# Link232-wifi.net
KiCad netlist of a schematic drawn in EAGLE
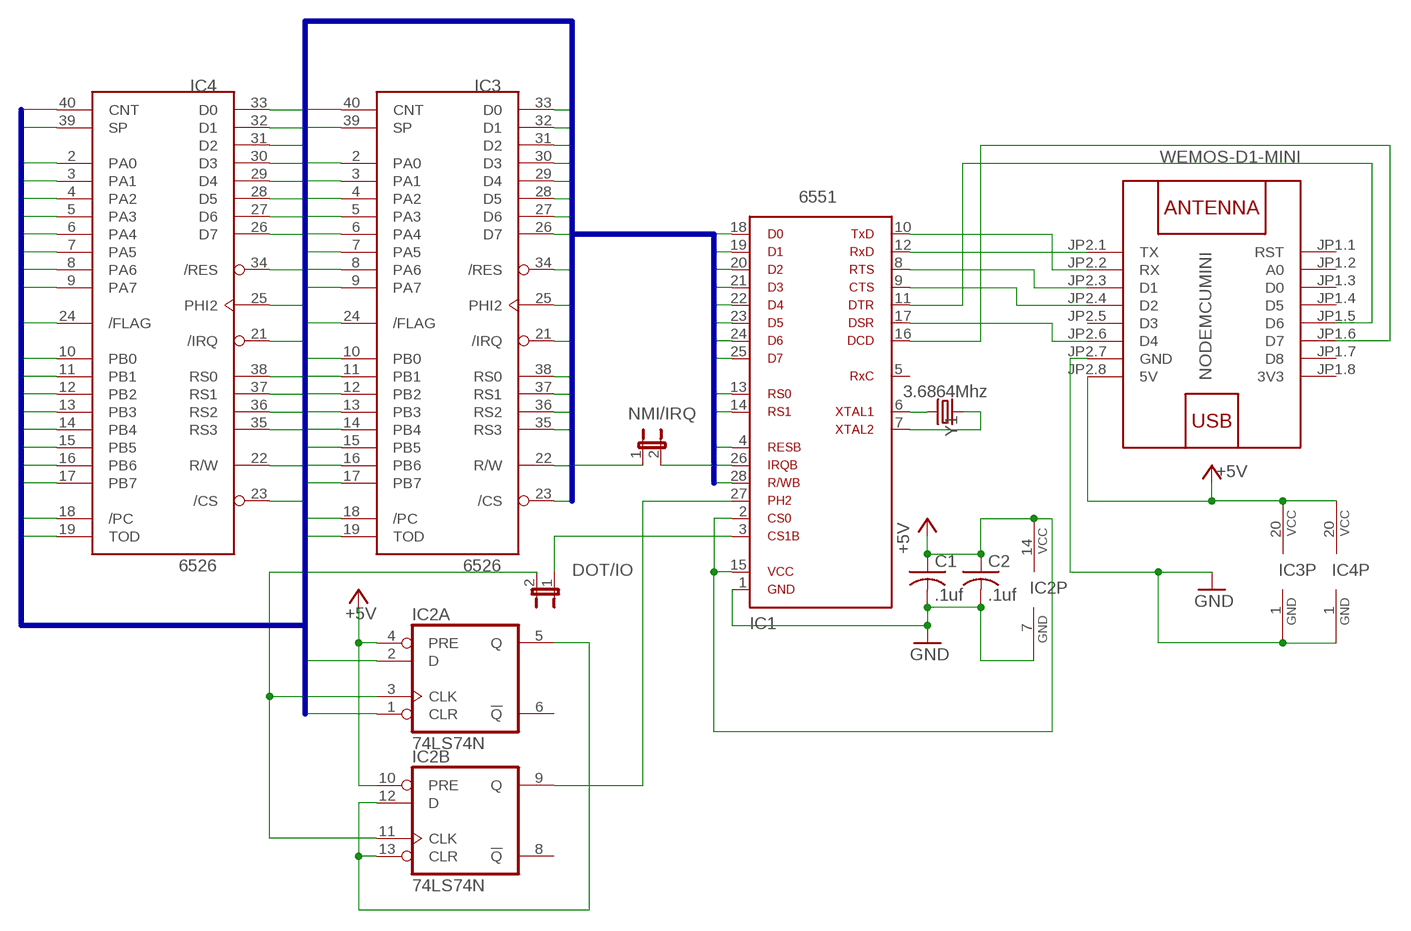
[diagram p0: schematic, sheet 1]

(export (version "E")
  (design (tool "Eeschema 10.0.6"))
  (components
    (comp (ref "C1")
      (value ".1uf")
      (footprint "eagle-import:C050-024X044")
      (libsource (lib "eagle-import") (part "C-US050-024X044"))
    )
    (comp (ref "C2")
      (value ".1uf")
      (footprint "eagle-import:C050-024X044")
      (libsource (lib "eagle-import") (part "C-US050-024X044"))
    )
    (comp (ref "IC1")
      (value "6551")
      (footprint "eagle-import:6551")
      (libsource (lib "eagle-import") (part "6551"))
    )
    (comp (ref "IC2")
      (value "74LS74N")
      (footprint "eagle-import:DIL14")
      (libsource (lib "eagle-import") (part "7474NLS"))
    )
    (comp (ref "IC3")
      (value "6526")
      (footprint "eagle-import:DIP40")
      (libsource (lib "eagle-import") (part "6526"))
    )
    (comp (ref "IC4")
      (value "6526")
      (footprint "eagle-import:DIP40")
      (libsource (lib "eagle-import") (part "6526"))
    )
    (comp (ref "JP1")
      (value "NMI/IRQ")
      (footprint "eagle-import:JP1")
      (libsource (lib "eagle-import") (part "JP1E"))
    )
    (comp (ref "JP2")
      (value "DOT/IO")
      (footprint "eagle-import:JP1")
      (libsource (lib "eagle-import") (part "JP1E"))
    )
    (comp (ref "NODEMCUMINI")
      (value "WEMOS-D1-MINI")
      (footprint "eagle-import:WEMOS-D1-MINI")
      (libsource (lib "eagle-import") (part "WEMOS-D1-MINI"))
    )
    (comp (ref "Y1")
      (value "3.6864Mhz")
      (footprint "eagle-import:HC49US")
      (libsource (lib "eagle-import") (part "CRYSTALPTH-HC49US"))
    )
  )
  (nets
    (net (code "1") (name "+5V") (class "Default")
      (node (ref "C1") (pin "1") (pinfunction "1_1") (pintype "passive"))
      (node (ref "C2") (pin "1") (pinfunction "1_1") (pintype "passive"))
      (node (ref "IC1") (pin "15") (pinfunction "15_15") (pintype "passive"))
      (node (ref "IC1") (pin "2") (pinfunction "2_2") (pintype "passive"))
      (node (ref "IC2") (pin "10") (pinfunction "PRE_10") (pintype "input"))
      (node (ref "IC2") (pin "14") (pinfunction "VCC_14") (pintype "power_in"))
      (node (ref "IC2") (pin "4") (pinfunction "PRE_4") (pintype "input"))
      (node (ref "IC3") (pin "20") (pinfunction "VCC_20") (pintype "power_in"))
      (node (ref "IC4") (pin "20") (pinfunction "VCC_20") (pintype "power_in"))
      (node (ref "NODEMCUMINI") (pin "JP2.8") (pinfunction "5V_JP2.8") (pintype "power_in"))
    )
    (net (code "2") (name "/3V3") (class "Default")
      (node (ref "NODEMCUMINI") (pin "JP1.8") (pinfunction "3V3_JP1.8") (pintype "power_in"))
    )
    (net (code "3") (name "/CNT") (class "Default")
      (node (ref "IC3") (pin "40") (pinfunction "CNT_40") (pintype "input"))
      (node (ref "IC4") (pin "40") (pinfunction "CNT_40") (pintype "input"))
    )
    (net (code "4") (name "/D0") (class "Default")
      (node (ref "IC1") (pin "18") (pinfunction "18_18") (pintype "passive"))
      (node (ref "IC3") (pin "33") (pinfunction "D0_33") (pintype "bidirectional"))
      (node (ref "IC4") (pin "33") (pinfunction "D0_33") (pintype "bidirectional"))
    )
    (net (code "5") (name "/D1") (class "Default")
      (node (ref "IC1") (pin "19") (pinfunction "19_19") (pintype "passive"))
      (node (ref "IC3") (pin "32") (pinfunction "D1_32") (pintype "bidirectional"))
      (node (ref "IC4") (pin "32") (pinfunction "D1_32") (pintype "bidirectional"))
    )
    (net (code "6") (name "/D2") (class "Default")
      (node (ref "IC1") (pin "20") (pinfunction "20_20") (pintype "passive"))
      (node (ref "IC3") (pin "31") (pinfunction "D2_31") (pintype "bidirectional"))
      (node (ref "IC4") (pin "31") (pinfunction "D2_31") (pintype "bidirectional"))
    )
    (net (code "7") (name "/D3") (class "Default")
      (node (ref "IC1") (pin "21") (pinfunction "21_21") (pintype "passive"))
      (node (ref "IC3") (pin "30") (pinfunction "D3_30") (pintype "bidirectional"))
      (node (ref "IC4") (pin "30") (pinfunction "D3_30") (pintype "bidirectional"))
    )
    (net (code "8") (name "/D4") (class "Default")
      (node (ref "IC1") (pin "22") (pinfunction "22_22") (pintype "passive"))
      (node (ref "IC3") (pin "29") (pinfunction "D4_29") (pintype "bidirectional"))
      (node (ref "IC4") (pin "29") (pinfunction "D4_29") (pintype "bidirectional"))
    )
    (net (code "9") (name "/D5") (class "Default")
      (node (ref "IC1") (pin "23") (pinfunction "23_23") (pintype "passive"))
      (node (ref "IC3") (pin "28") (pinfunction "D5_28") (pintype "bidirectional"))
      (node (ref "IC4") (pin "28") (pinfunction "D5_28") (pintype "bidirectional"))
    )
    (net (code "10") (name "/D6") (class "Default")
      (node (ref "IC1") (pin "24") (pinfunction "24_24") (pintype "passive"))
      (node (ref "IC3") (pin "27") (pinfunction "D6_27") (pintype "bidirectional"))
      (node (ref "IC4") (pin "27") (pinfunction "D6_27") (pintype "bidirectional"))
    )
    (net (code "11") (name "/D7") (class "Default")
      (node (ref "IC1") (pin "25") (pinfunction "25_25") (pintype "passive"))
      (node (ref "IC3") (pin "26") (pinfunction "D7_26") (pintype "bidirectional"))
      (node (ref "IC4") (pin "26") (pinfunction "D7_26") (pintype "bidirectional"))
    )
    (net (code "12") (name "/IRQ") (class "Default")
      (node (ref "IC3") (pin "21") (pinfunction "/IRQ_21") (pintype "open_collector"))
      (node (ref "IC4") (pin "21") (pinfunction "/IRQ_21") (pintype "open_collector"))
      (node (ref "JP1") (pin "1") (pinfunction "1_1") (pintype "passive"))
    )
    (net (code "13") (name "/PA0") (class "Default")
      (node (ref "IC3") (pin "2") (pinfunction "PA0_2") (pintype "bidirectional"))
      (node (ref "IC4") (pin "2") (pinfunction "PA0_2") (pintype "bidirectional"))
    )
    (net (code "14") (name "/PA1") (class "Default")
      (node (ref "IC3") (pin "3") (pinfunction "PA1_3") (pintype "bidirectional"))
      (node (ref "IC4") (pin "3") (pinfunction "PA1_3") (pintype "bidirectional"))
    )
    (net (code "15") (name "/PA2") (class "Default")
      (node (ref "IC3") (pin "4") (pinfunction "PA2_4") (pintype "bidirectional"))
      (node (ref "IC4") (pin "4") (pinfunction "PA2_4") (pintype "bidirectional"))
    )
    (net (code "16") (name "/PA3") (class "Default")
      (node (ref "IC3") (pin "5") (pinfunction "PA3_5") (pintype "bidirectional"))
      (node (ref "IC4") (pin "5") (pinfunction "PA3_5") (pintype "bidirectional"))
    )
    (net (code "17") (name "/PA4") (class "Default")
      (node (ref "IC3") (pin "6") (pinfunction "PA4_6") (pintype "bidirectional"))
      (node (ref "IC4") (pin "6") (pinfunction "PA4_6") (pintype "bidirectional"))
    )
    (net (code "18") (name "/PA5") (class "Default")
      (node (ref "IC3") (pin "7") (pinfunction "PA5_7") (pintype "bidirectional"))
      (node (ref "IC4") (pin "7") (pinfunction "PA5_7") (pintype "bidirectional"))
    )
    (net (code "19") (name "/PA6") (class "Default")
      (node (ref "IC3") (pin "8") (pinfunction "PA6_8") (pintype "bidirectional"))
      (node (ref "IC4") (pin "8") (pinfunction "PA6_8") (pintype "bidirectional"))
    )
    (net (code "20") (name "/PA7") (class "Default")
      (node (ref "IC3") (pin "9") (pinfunction "PA7_9") (pintype "bidirectional"))
      (node (ref "IC4") (pin "9") (pinfunction "PA7_9") (pintype "bidirectional"))
    )
    (net (code "21") (name "/PB0") (class "Default")
      (node (ref "IC3") (pin "10") (pinfunction "PB0_10") (pintype "bidirectional"))
      (node (ref "IC4") (pin "10") (pinfunction "PB0_10") (pintype "bidirectional"))
    )
    (net (code "22") (name "/PB1") (class "Default")
      (node (ref "IC3") (pin "11") (pinfunction "PB1_11") (pintype "bidirectional"))
      (node (ref "IC4") (pin "11") (pinfunction "PB1_11") (pintype "bidirectional"))
    )
    (net (code "23") (name "/PB2") (class "Default")
      (node (ref "IC3") (pin "12") (pinfunction "PB2_12") (pintype "bidirectional"))
      (node (ref "IC4") (pin "12") (pinfunction "PB2_12") (pintype "bidirectional"))
    )
    (net (code "24") (name "/PB3") (class "Default")
      (node (ref "IC3") (pin "13") (pinfunction "PB3_13") (pintype "bidirectional"))
      (node (ref "IC4") (pin "13") (pinfunction "PB3_13") (pintype "bidirectional"))
    )
    (net (code "25") (name "/PB4") (class "Default")
      (node (ref "IC3") (pin "14") (pinfunction "PB4_14") (pintype "bidirectional"))
      (node (ref "IC4") (pin "14") (pinfunction "PB4_14") (pintype "bidirectional"))
    )
    (net (code "26") (name "/PB5") (class "Default")
      (node (ref "IC3") (pin "15") (pinfunction "PB5_15") (pintype "bidirectional"))
      (node (ref "IC4") (pin "15") (pinfunction "PB5_15") (pintype "bidirectional"))
    )
    (net (code "27") (name "/PB6") (class "Default")
      (node (ref "IC3") (pin "16") (pinfunction "PB6_16") (pintype "bidirectional"))
      (node (ref "IC4") (pin "16") (pinfunction "PB6_16") (pintype "bidirectional"))
    )
    (net (code "28") (name "/PB7") (class "Default")
      (node (ref "IC3") (pin "17") (pinfunction "PB7_17") (pintype "bidirectional"))
      (node (ref "IC4") (pin "17") (pinfunction "PB7_17") (pintype "bidirectional"))
    )
    (net (code "29") (name "/PHI2") (class "Default")
      (node (ref "IC2") (pin "1") (pinfunction "CLR_1") (pintype "input"))
      (node (ref "IC2") (pin "2") (pinfunction "D_2") (pintype "input"))
      (node (ref "IC3") (pin "25") (pinfunction "PHI2_25") (pintype "input"))
      (node (ref "IC4") (pin "25") (pinfunction "PHI2_25") (pintype "input"))
    )
    (net (code "30") (name "/RES") (class "Default")
      (node (ref "IC1") (pin "4") (pinfunction "4_4") (pintype "passive"))
      (node (ref "IC3") (pin "34") (pinfunction "/RES_34") (pintype "input"))
      (node (ref "IC4") (pin "34") (pinfunction "/RES_34") (pintype "input"))
    )
    (net (code "31") (name "/RS0") (class "Default")
      (node (ref "IC1") (pin "13") (pinfunction "13_13") (pintype "passive"))
      (node (ref "IC3") (pin "38") (pinfunction "RS0_38") (pintype "input"))
      (node (ref "IC4") (pin "38") (pinfunction "RS0_38") (pintype "input"))
    )
    (net (code "32") (name "/RS1") (class "Default")
      (node (ref "IC1") (pin "14") (pinfunction "14_14") (pintype "passive"))
      (node (ref "IC3") (pin "37") (pinfunction "RS1_37") (pintype "input"))
      (node (ref "IC4") (pin "37") (pinfunction "RS1_37") (pintype "input"))
    )
    (net (code "33") (name "/RS2") (class "Default")
      (node (ref "IC3") (pin "36") (pinfunction "RS2_36") (pintype "input"))
      (node (ref "IC4") (pin "36") (pinfunction "RS2_36") (pintype "input"))
    )
    (net (code "34") (name "/RS3") (class "Default")
      (node (ref "IC3") (pin "35") (pinfunction "RS3_35") (pintype "input"))
      (node (ref "IC4") (pin "35") (pinfunction "RS3_35") (pintype "input"))
    )
    (net (code "35") (name "/RW") (class "Default")
      (node (ref "IC1") (pin "28") (pinfunction "28_28") (pintype "passive"))
      (node (ref "IC3") (pin "22") (pinfunction "R/W_22") (pintype "input"))
      (node (ref "IC4") (pin "22") (pinfunction "R/W_22") (pintype "input"))
    )
    (net (code "36") (name "/SP") (class "Default")
      (node (ref "IC3") (pin "39") (pinfunction "SP_39") (pintype "bidirectional"))
      (node (ref "IC4") (pin "39") (pinfunction "SP_39") (pintype "bidirectional"))
    )
    (net (code "37") (name "/TOD") (class "Default")
      (node (ref "IC3") (pin "19") (pinfunction "TOD_19") (pintype "bidirectional"))
      (node (ref "IC4") (pin "19") (pinfunction "TOD_19") (pintype "bidirectional"))
    )
    (net (code "38") (name "/{slash}CS") (class "Default")
      (node (ref "IC3") (pin "23") (pinfunction "/CS_23") (pintype "input"))
      (node (ref "IC4") (pin "23") (pinfunction "/CS_23") (pintype "input"))
    )
    (net (code "39") (name "/{slash}FLAG") (class "Default")
      (node (ref "IC3") (pin "24") (pinfunction "/FLAG_24") (pintype "input"))
      (node (ref "IC4") (pin "24") (pinfunction "/FLAG_24") (pintype "input"))
    )
    (net (code "40") (name "/{slash}PC") (class "Default")
      (node (ref "IC3") (pin "18") (pinfunction "/PC_18") (pintype "bidirectional"))
      (node (ref "IC4") (pin "18") (pinfunction "/PC_18") (pintype "bidirectional"))
    )
    (net (code "41") (name "GND") (class "Default")
      (node (ref "C1") (pin "2") (pinfunction "2_2") (pintype "passive"))
      (node (ref "C2") (pin "2") (pinfunction "2_2") (pintype "passive"))
      (node (ref "IC1") (pin "1") (pinfunction "1_1") (pintype "passive"))
      (node (ref "IC2") (pin "7") (pinfunction "GND_7") (pintype "power_in"))
      (node (ref "IC3") (pin "1") (pinfunction "GND_1") (pintype "power_in"))
      (node (ref "IC4") (pin "1") (pinfunction "GND_1") (pintype "power_in"))
      (node (ref "NODEMCUMINI") (pin "JP2.7") (pinfunction "GND_JP2.7") (pintype "power_in"))
    )
    (net (code "42") (name "Net-(IC1-Pad3)") (class "Default")
      (node (ref "IC1") (pin "3") (pinfunction "3_3") (pintype "passive"))
      (node (ref "JP2") (pin "1") (pinfunction "1_1") (pintype "passive"))
    )
    (net (code "43") (name "Net-(IC1-Pad6)") (class "Default")
      (node (ref "IC1") (pin "6") (pinfunction "6_6") (pintype "passive"))
      (node (ref "Y1") (pin "2") (pinfunction "2_2") (pintype "passive"))
    )
    (net (code "44") (name "Net-(IC1-Pad7)") (class "Default")
      (node (ref "IC1") (pin "7") (pinfunction "7_7") (pintype "passive"))
      (node (ref "Y1") (pin "1") (pinfunction "1_1") (pintype "passive"))
    )
    (net (code "45") (name "Net-(IC1-Pad26)") (class "Default")
      (node (ref "IC1") (pin "26") (pinfunction "26_26") (pintype "passive"))
      (node (ref "JP1") (pin "2") (pinfunction "2_2") (pintype "passive"))
    )
    (net (code "46") (name "Net-(IC2A-CLK)") (class "Default")
      (node (ref "IC2") (pin "11") (pinfunction "CLK_11") (pintype "input"))
      (node (ref "IC2") (pin "3") (pinfunction "CLK_3") (pintype "input"))
      (node (ref "JP2") (pin "2") (pinfunction "2_2") (pintype "passive"))
    )
    (net (code "47") (name "Net-(IC2A-Q)") (class "Default")
      (node (ref "IC2") (pin "12") (pinfunction "D_12") (pintype "input"))
      (node (ref "IC2") (pin "13") (pinfunction "CLR_13") (pintype "input"))
      (node (ref "IC2") (pin "5") (pinfunction "Q_5") (pintype "output"))
    )
    (net (code "48") (name "Net-(IC2B-Q)") (class "Default")
      (node (ref "IC1") (pin "27") (pinfunction "27_27") (pintype "passive"))
      (node (ref "IC2") (pin "9") (pinfunction "Q_9") (pintype "output"))
    )
    (net (code "49") (name "Net-(NODEMCUMINI-D1)") (class "Default")
      (node (ref "IC1") (pin "8") (pinfunction "8_8") (pintype "passive"))
      (node (ref "NODEMCUMINI") (pin "JP2.3") (pinfunction "D1_JP2.3") (pintype "bidirectional"))
    )
    (net (code "50") (name "Net-(NODEMCUMINI-D2)") (class "Default")
      (node (ref "IC1") (pin "9") (pinfunction "9_9") (pintype "passive"))
      (node (ref "NODEMCUMINI") (pin "JP2.4") (pinfunction "D2_JP2.4") (pintype "bidirectional"))
    )
    (net (code "51") (name "Net-(NODEMCUMINI-D4)") (class "Default")
      (node (ref "IC1") (pin "17") (pinfunction "17_17") (pintype "passive"))
      (node (ref "NODEMCUMINI") (pin "JP2.6") (pinfunction "D4_JP2.6") (pintype "bidirectional"))
    )
    (net (code "52") (name "Net-(NODEMCUMINI-D6)") (class "Default")
      (node (ref "IC1") (pin "11") (pinfunction "11_11") (pintype "passive"))
      (node (ref "NODEMCUMINI") (pin "JP1.5") (pinfunction "D6_JP1.5") (pintype "bidirectional"))
    )
    (net (code "53") (name "Net-(NODEMCUMINI-D7)") (class "Default")
      (node (ref "IC1") (pin "16") (pinfunction "16_16") (pintype "passive"))
      (node (ref "NODEMCUMINI") (pin "JP1.6") (pinfunction "D7_JP1.6") (pintype "bidirectional"))
    )
    (net (code "54") (name "Net-(NODEMCUMINI-RX)") (class "Default")
      (node (ref "IC1") (pin "10") (pinfunction "10_10") (pintype "passive"))
      (node (ref "NODEMCUMINI") (pin "JP2.2") (pinfunction "RX_JP2.2") (pintype "bidirectional"))
    )
    (net (code "55") (name "Net-(NODEMCUMINI-TX)") (class "Default")
      (node (ref "IC1") (pin "12") (pinfunction "12_12") (pintype "passive"))
      (node (ref "NODEMCUMINI") (pin "JP2.1") (pinfunction "TX_JP2.1") (pintype "bidirectional"))
    )
    (net (code "56") (name "unconnected-(IC1-Pad5)") (class "Default")
      (node (ref "IC1") (pin "5") (pinfunction "5_5") (pintype "passive"))
    )
    (net (code "57") (name "unconnected-(IC2A-~{Q}-Pad6)") (class "Default")
      (node (ref "IC2") (pin "6") (pinfunction "~{Q}_6") (pintype "output"))
    )
    (net (code "58") (name "unconnected-(IC2B-~{Q}-Pad8)") (class "Default")
      (node (ref "IC2") (pin "8") (pinfunction "~{Q}_8") (pintype "output"))
    )
    (net (code "59") (name "unconnected-(NODEMCUMINI-A0-PadJP1.2)") (class "Default")
      (node (ref "NODEMCUMINI") (pin "JP1.2") (pinfunction "A0_JP1.2") (pintype "bidirectional"))
    )
    (net (code "60") (name "unconnected-(NODEMCUMINI-D0-PadJP1.3)") (class "Default")
      (node (ref "NODEMCUMINI") (pin "JP1.3") (pinfunction "D0_JP1.3") (pintype "bidirectional"))
    )
    (net (code "61") (name "unconnected-(NODEMCUMINI-D3-PadJP2.5)") (class "Default")
      (node (ref "NODEMCUMINI") (pin "JP2.5") (pinfunction "D3_JP2.5") (pintype "bidirectional"))
    )
    (net (code "62") (name "unconnected-(NODEMCUMINI-D5-PadJP1.4)") (class "Default")
      (node (ref "NODEMCUMINI") (pin "JP1.4") (pinfunction "D5_JP1.4") (pintype "bidirectional"))
    )
    (net (code "63") (name "unconnected-(NODEMCUMINI-D8-PadJP1.7)") (class "Default")
      (node (ref "NODEMCUMINI") (pin "JP1.7") (pinfunction "D8_JP1.7") (pintype "bidirectional"))
    )
    (net (code "64") (name "unconnected-(NODEMCUMINI-RST-PadJP1.1)") (class "Default")
      (node (ref "NODEMCUMINI") (pin "JP1.1") (pinfunction "RST_JP1.1") (pintype "bidirectional"))
    )
  )
)
